# pov-globe2.net
KiCad netlist of a schematic drawn in EAGLE
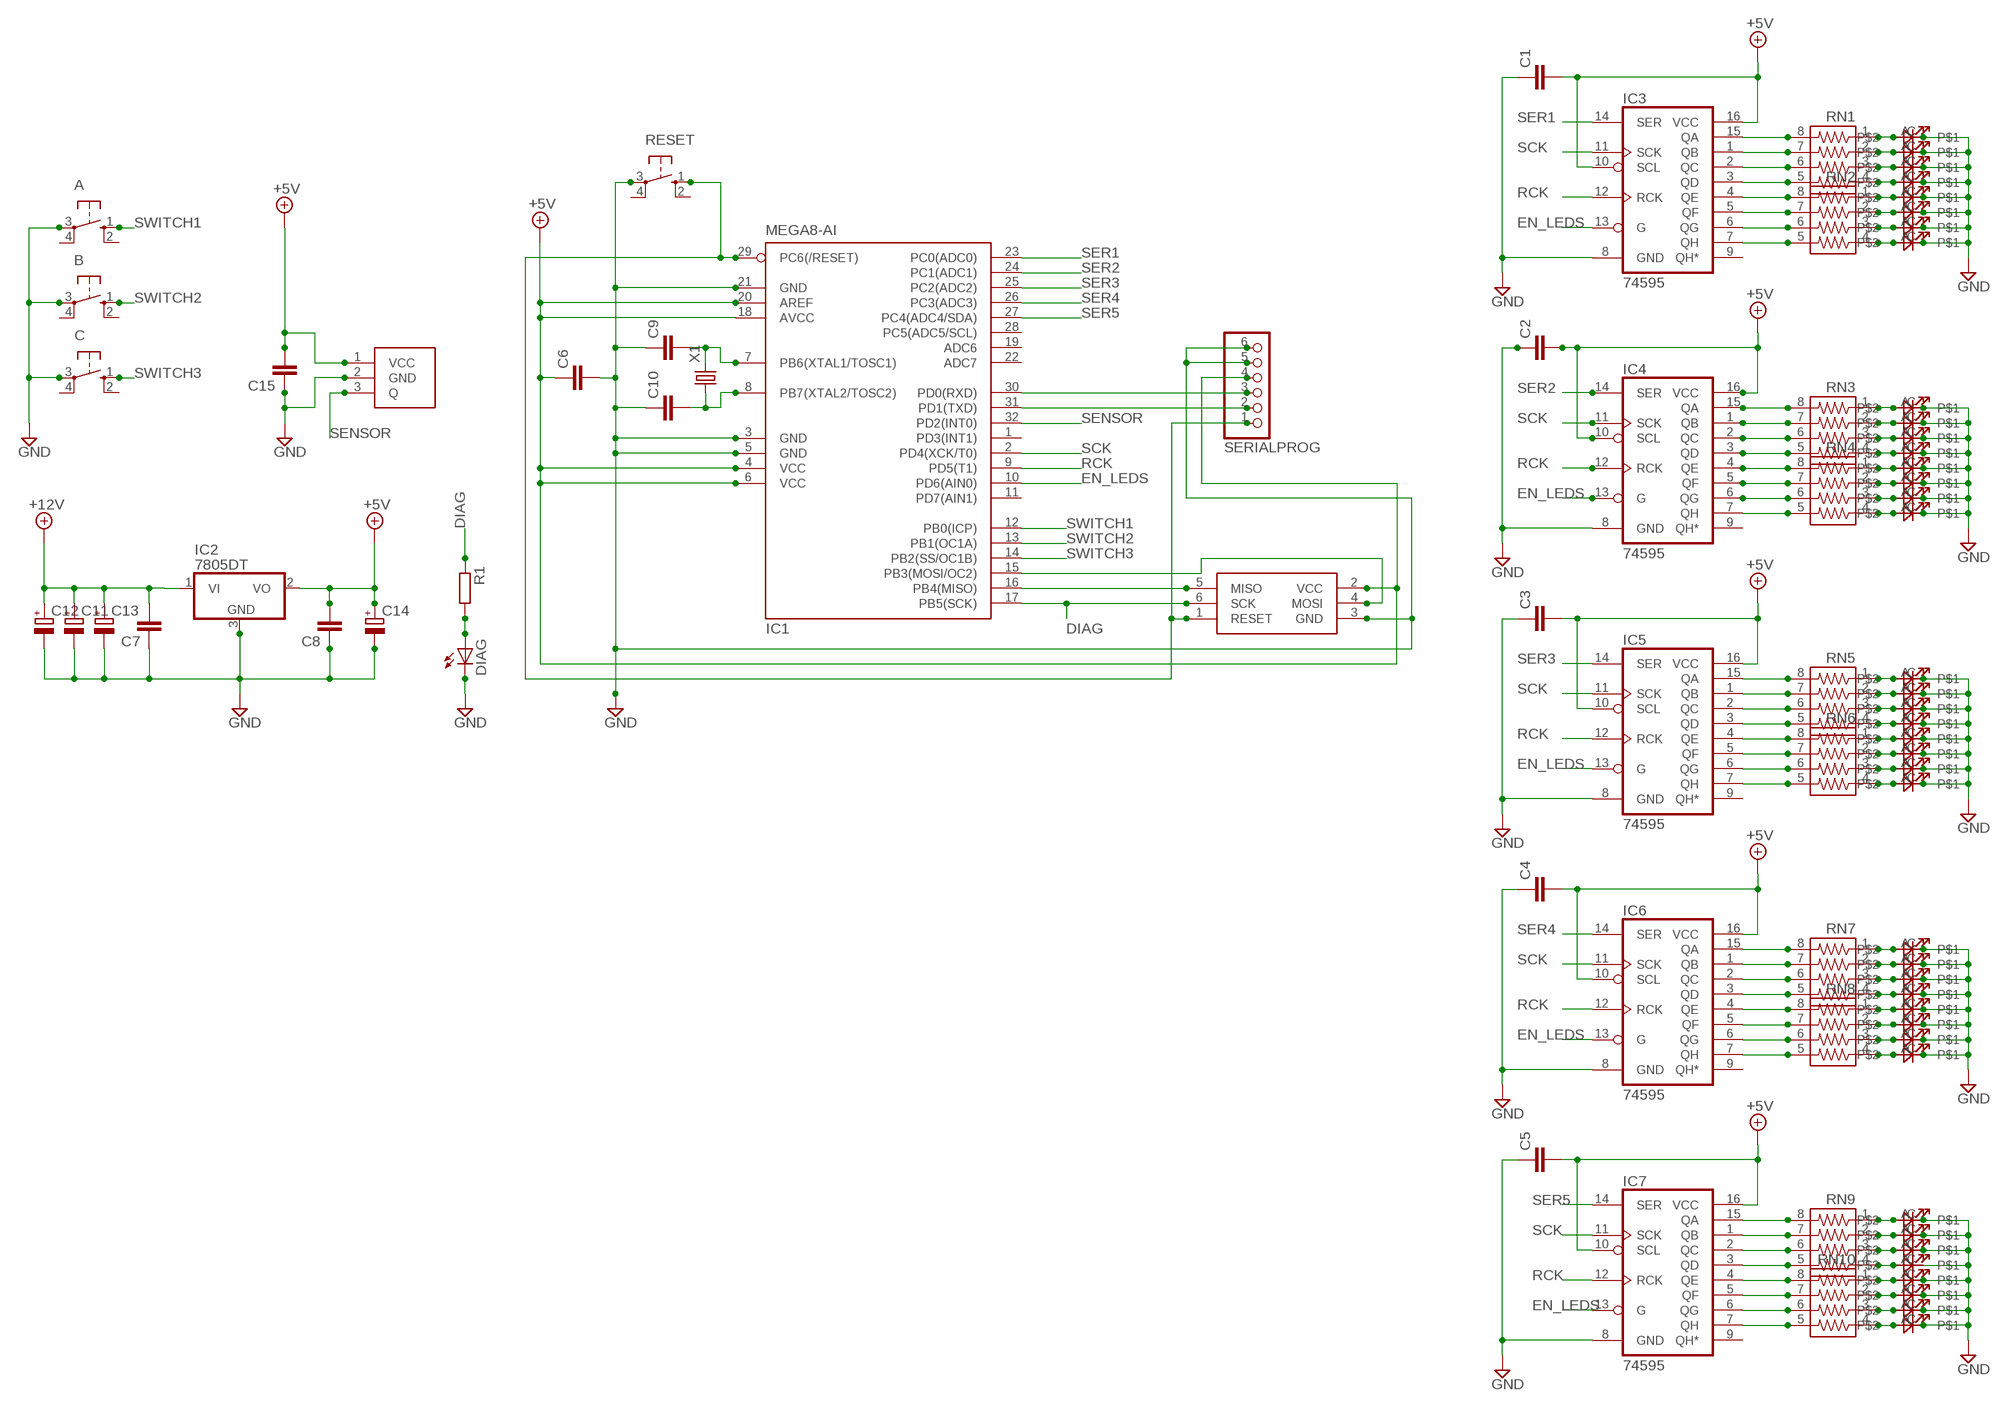
[diagram p0: schematic, sheet 1]

(export (version "E")
  (design (tool "Eeschema 10.0.6"))
  (components
    (comp (ref "0")
      (value "3MMLEDSIDELED1_8MMSIDE")
      (footprint "eagle-import:LED1_8MMSIDE")
      (libsource (lib "eagle-import") (part "3MMLEDSIDELED1_8MMSIDE"))
    )
    (comp (ref "1")
      (value "3MMLEDSIDELED1_8MMSIDE")
      (footprint "eagle-import:LED1_8MMSIDE")
      (libsource (lib "eagle-import") (part "3MMLEDSIDELED1_8MMSIDE"))
    )
    (comp (ref "2")
      (value "3MMLEDSIDELED1_8MMSIDE")
      (footprint "eagle-import:LED1_8MMSIDE")
      (libsource (lib "eagle-import") (part "3MMLEDSIDELED1_8MMSIDE"))
    )
    (comp (ref "3")
      (value "3MMLEDSIDELED1_8MMSIDE")
      (footprint "eagle-import:LED1_8MMSIDE")
      (libsource (lib "eagle-import") (part "3MMLEDSIDELED1_8MMSIDE"))
    )
    (comp (ref "4")
      (value "3MMLEDSIDELED1_8MMSIDE")
      (footprint "eagle-import:LED1_8MMSIDE")
      (libsource (lib "eagle-import") (part "3MMLEDSIDELED1_8MMSIDE"))
    )
    (comp (ref "5")
      (value "3MMLEDSIDELED1_8MMSIDE")
      (footprint "eagle-import:LED1_8MMSIDE")
      (libsource (lib "eagle-import") (part "3MMLEDSIDELED1_8MMSIDE"))
    )
    (comp (ref "6")
      (value "3MMLEDSIDELED1_8MMSIDE")
      (footprint "eagle-import:LED1_8MMSIDE")
      (libsource (lib "eagle-import") (part "3MMLEDSIDELED1_8MMSIDE"))
    )
    (comp (ref "7")
      (value "3MMLEDSIDELED1_8MMSIDE")
      (footprint "eagle-import:LED1_8MMSIDE")
      (libsource (lib "eagle-import") (part "3MMLEDSIDELED1_8MMSIDE"))
    )
    (comp (ref "8")
      (value "3MMLEDSIDELED1_8MMSIDE")
      (footprint "eagle-import:LED1_8MMSIDE")
      (libsource (lib "eagle-import") (part "3MMLEDSIDELED1_8MMSIDE"))
    )
    (comp (ref "9")
      (value "3MMLEDSIDELED1_8MMSIDE")
      (footprint "eagle-import:LED1_8MMSIDE")
      (libsource (lib "eagle-import") (part "3MMLEDSIDELED1_8MMSIDE"))
    )
    (comp (ref "10")
      (value "3MMLEDSIDELED1_8MMSIDE")
      (footprint "eagle-import:LED1_8MMSIDE")
      (libsource (lib "eagle-import") (part "3MMLEDSIDELED1_8MMSIDE"))
    )
    (comp (ref "11")
      (value "3MMLEDSIDELED1_8MMSIDE")
      (footprint "eagle-import:LED1_8MMSIDE")
      (libsource (lib "eagle-import") (part "3MMLEDSIDELED1_8MMSIDE"))
    )
    (comp (ref "12")
      (value "3MMLEDSIDELED1_8MMSIDE")
      (footprint "eagle-import:LED1_8MMSIDE")
      (libsource (lib "eagle-import") (part "3MMLEDSIDELED1_8MMSIDE"))
    )
    (comp (ref "13")
      (value "3MMLEDSIDELED1_8MMSIDE")
      (footprint "eagle-import:LED1_8MMSIDE")
      (libsource (lib "eagle-import") (part "3MMLEDSIDELED1_8MMSIDE"))
    )
    (comp (ref "14")
      (value "3MMLEDSIDELED1_8MMSIDE")
      (footprint "eagle-import:LED1_8MMSIDE")
      (libsource (lib "eagle-import") (part "3MMLEDSIDELED1_8MMSIDE"))
    )
    (comp (ref "15")
      (value "3MMLEDSIDELED1_8MMSIDE")
      (footprint "eagle-import:LED1_8MMSIDE")
      (libsource (lib "eagle-import") (part "3MMLEDSIDELED1_8MMSIDE"))
    )
    (comp (ref "16")
      (value "3MMLEDSIDELED1_8MMSIDE")
      (footprint "eagle-import:LED1_8MMSIDE")
      (libsource (lib "eagle-import") (part "3MMLEDSIDELED1_8MMSIDE"))
    )
    (comp (ref "17")
      (value "3MMLEDSIDELED1_8MMSIDE")
      (footprint "eagle-import:LED1_8MMSIDE")
      (libsource (lib "eagle-import") (part "3MMLEDSIDELED1_8MMSIDE"))
    )
    (comp (ref "18")
      (value "3MMLEDSIDELED1_8MMSIDE")
      (footprint "eagle-import:LED1_8MMSIDE")
      (libsource (lib "eagle-import") (part "3MMLEDSIDELED1_8MMSIDE"))
    )
    (comp (ref "19")
      (value "3MMLEDSIDELED1_8MMSIDE")
      (footprint "eagle-import:LED1_8MMSIDE")
      (libsource (lib "eagle-import") (part "3MMLEDSIDELED1_8MMSIDE"))
    )
    (comp (ref "20")
      (value "3MMLEDSIDELED1_8MMSIDE")
      (footprint "eagle-import:LED1_8MMSIDE")
      (libsource (lib "eagle-import") (part "3MMLEDSIDELED1_8MMSIDE"))
    )
    (comp (ref "21")
      (value "3MMLEDSIDELED1_8MMSIDE")
      (footprint "eagle-import:LED1_8MMSIDE")
      (libsource (lib "eagle-import") (part "3MMLEDSIDELED1_8MMSIDE"))
    )
    (comp (ref "22")
      (value "3MMLEDSIDELED1_8MMSIDE")
      (footprint "eagle-import:LED1_8MMSIDE")
      (libsource (lib "eagle-import") (part "3MMLEDSIDELED1_8MMSIDE"))
    )
    (comp (ref "23")
      (value "3MMLEDSIDELED1_8MMSIDE")
      (footprint "eagle-import:LED1_8MMSIDE")
      (libsource (lib "eagle-import") (part "3MMLEDSIDELED1_8MMSIDE"))
    )
    (comp (ref "24")
      (value "3MMLEDSIDELED1_8MMSIDE")
      (footprint "eagle-import:LED1_8MMSIDE")
      (libsource (lib "eagle-import") (part "3MMLEDSIDELED1_8MMSIDE"))
    )
    (comp (ref "25")
      (value "3MMLEDSIDELED1_8MMSIDE")
      (footprint "eagle-import:LED1_8MMSIDE")
      (libsource (lib "eagle-import") (part "3MMLEDSIDELED1_8MMSIDE"))
    )
    (comp (ref "26")
      (value "3MMLEDSIDELED1_8MMSIDE")
      (footprint "eagle-import:LED1_8MMSIDE")
      (libsource (lib "eagle-import") (part "3MMLEDSIDELED1_8MMSIDE"))
    )
    (comp (ref "27")
      (value "3MMLEDSIDELED1_8MMSIDE")
      (footprint "eagle-import:LED1_8MMSIDE")
      (libsource (lib "eagle-import") (part "3MMLEDSIDELED1_8MMSIDE"))
    )
    (comp (ref "28")
      (value "3MMLEDSIDELED1_8MMSIDE")
      (footprint "eagle-import:LED1_8MMSIDE")
      (libsource (lib "eagle-import") (part "3MMLEDSIDELED1_8MMSIDE"))
    )
    (comp (ref "29")
      (value "3MMLEDSIDELED1_8MMSIDE")
      (footprint "eagle-import:LED1_8MMSIDE")
      (libsource (lib "eagle-import") (part "3MMLEDSIDELED1_8MMSIDE"))
    )
    (comp (ref "30")
      (value "3MMLEDSIDELED1_8MMSIDE")
      (footprint "eagle-import:LED1_8MMSIDE")
      (libsource (lib "eagle-import") (part "3MMLEDSIDELED1_8MMSIDE"))
    )
    (comp (ref "31")
      (value "3MMLEDSIDELED1_8MMSIDE")
      (footprint "eagle-import:LED1_8MMSIDE")
      (libsource (lib "eagle-import") (part "3MMLEDSIDELED1_8MMSIDE"))
    )
    (comp (ref "32")
      (value "3MMLEDSIDELED1_8MMSIDE")
      (footprint "eagle-import:LED1_8MMSIDE")
      (libsource (lib "eagle-import") (part "3MMLEDSIDELED1_8MMSIDE"))
    )
    (comp (ref "33")
      (value "3MMLEDSIDELED1_8MMSIDE")
      (footprint "eagle-import:LED1_8MMSIDE")
      (libsource (lib "eagle-import") (part "3MMLEDSIDELED1_8MMSIDE"))
    )
    (comp (ref "34")
      (value "3MMLEDSIDELED1_8MMSIDE")
      (footprint "eagle-import:LED1_8MMSIDE")
      (libsource (lib "eagle-import") (part "3MMLEDSIDELED1_8MMSIDE"))
    )
    (comp (ref "35")
      (value "3MMLEDSIDELED1_8MMSIDE")
      (footprint "eagle-import:LED1_8MMSIDE")
      (libsource (lib "eagle-import") (part "3MMLEDSIDELED1_8MMSIDE"))
    )
    (comp (ref "36")
      (value "3MMLEDSIDELED1_8MMSIDE")
      (footprint "eagle-import:LED1_8MMSIDE")
      (libsource (lib "eagle-import") (part "3MMLEDSIDELED1_8MMSIDE"))
    )
    (comp (ref "37")
      (value "3MMLEDSIDELED1_8MMSIDE")
      (footprint "eagle-import:LED1_8MMSIDE")
      (libsource (lib "eagle-import") (part "3MMLEDSIDELED1_8MMSIDE"))
    )
    (comp (ref "38")
      (value "3MMLEDSIDELED1_8MMSIDE")
      (footprint "eagle-import:LED1_8MMSIDE")
      (libsource (lib "eagle-import") (part "3MMLEDSIDELED1_8MMSIDE"))
    )
    (comp (ref "39")
      (value "3MMLEDSIDELED1_8MMSIDE")
      (footprint "eagle-import:LED1_8MMSIDE")
      (libsource (lib "eagle-import") (part "3MMLEDSIDELED1_8MMSIDE"))
    )
    (comp (ref "A")
      (value "10-XX")
      (footprint "eagle-import:B3F-10XX")
      (libsource (lib "eagle-import") (part "10-XX"))
    )
    (comp (ref "B")
      (value "10-XX")
      (footprint "eagle-import:B3F-10XX")
      (libsource (lib "eagle-import") (part "10-XX"))
    )
    (comp (ref "C")
      (value "10-XX")
      (footprint "eagle-import:B3F-10XX")
      (libsource (lib "eagle-import") (part "10-XX"))
    )
    (comp (ref "C1")
      (value "C-EUC0805")
      (footprint "eagle-import:C0805")
      (libsource (lib "eagle-import") (part "C-EUC0805"))
    )
    (comp (ref "C2")
      (value "C-EUC0805")
      (footprint "eagle-import:C0805")
      (libsource (lib "eagle-import") (part "C-EUC0805"))
    )
    (comp (ref "C3")
      (value "C-EUC0805")
      (footprint "eagle-import:C0805")
      (libsource (lib "eagle-import") (part "C-EUC0805"))
    )
    (comp (ref "C4")
      (value "C-EUC0805")
      (footprint "eagle-import:C0805")
      (libsource (lib "eagle-import") (part "C-EUC0805"))
    )
    (comp (ref "C5")
      (value "C-EUC0805")
      (footprint "eagle-import:C0805")
      (libsource (lib "eagle-import") (part "C-EUC0805"))
    )
    (comp (ref "C6")
      (value "C-EUC0805")
      (footprint "eagle-import:C0805")
      (libsource (lib "eagle-import") (part "C-EUC0805"))
    )
    (comp (ref "C7")
      (value "C-EUC0805")
      (footprint "eagle-import:C0805")
      (libsource (lib "eagle-import") (part "C-EUC0805"))
    )
    (comp (ref "C8")
      (value "C-EUC0805")
      (footprint "eagle-import:C0805")
      (libsource (lib "eagle-import") (part "C-EUC0805"))
    )
    (comp (ref "C9")
      (value "C-EUC0805")
      (footprint "eagle-import:C0805")
      (libsource (lib "eagle-import") (part "C-EUC0805"))
    )
    (comp (ref "C10")
      (value "C-EUC0805")
      (footprint "eagle-import:C0805")
      (libsource (lib "eagle-import") (part "C-EUC0805"))
    )
    (comp (ref "C11")
      (value "CPOL-EUE2-5")
      (footprint "eagle-import:E2-5")
      (libsource (lib "eagle-import") (part "CPOL-EUE2-5"))
    )
    (comp (ref "C12")
      (value "CPOL-EUE2-5")
      (footprint "eagle-import:E2-5")
      (libsource (lib "eagle-import") (part "CPOL-EUE2-5"))
    )
    (comp (ref "C13")
      (value "CPOL-EUE2-5")
      (footprint "eagle-import:E2-5")
      (libsource (lib "eagle-import") (part "CPOL-EUE2-5"))
    )
    (comp (ref "C14")
      (value "CPOL-EUE2-5")
      (footprint "eagle-import:E2-5")
      (libsource (lib "eagle-import") (part "CPOL-EUE2-5"))
    )
    (comp (ref "C15")
      (value "C-EUC0805")
      (footprint "eagle-import:C0805")
      (libsource (lib "eagle-import") (part "C-EUC0805"))
    )
    (comp (ref "DIAG")
      (value "LEDCHIP-LED0805")
      (footprint "eagle-import:CHIP-LED0805")
      (libsource (lib "eagle-import") (part "LEDCHIP-LED0805"))
    )
    (comp (ref "IC1")
      (value "MEGA8-AI")
      (footprint "eagle-import:TQFP32-08")
      (libsource (lib "eagle-import") (part "MEGA8-AI"))
    )
    (comp (ref "IC2")
      (value "7805DT")
      (footprint "eagle-import:TO252")
      (libsource (lib "eagle-import") (part "78DT05"))
    )
    (comp (ref "IC3")
      (value "74595")
      (footprint "eagle-import:TSSOP16")
      (libsource (lib "eagle-import") (part "74595"))
    )
    (comp (ref "IC4")
      (value "74595")
      (footprint "eagle-import:TSSOP16")
      (libsource (lib "eagle-import") (part "74595"))
    )
    (comp (ref "IC5")
      (value "74595")
      (footprint "eagle-import:TSSOP16")
      (libsource (lib "eagle-import") (part "74595"))
    )
    (comp (ref "IC6")
      (value "74595")
      (footprint "eagle-import:TSSOP16")
      (libsource (lib "eagle-import") (part "74595"))
    )
    (comp (ref "IC7")
      (value "74595")
      (footprint "eagle-import:TSSOP16")
      (libsource (lib "eagle-import") (part "74595"))
    )
    (comp (ref "ICSP")
      (value "TAG_CONN_AVR")
      (footprint "eagle-import:TC2030-MCP-NL")
      (libsource (lib "eagle-import") (part "TAG_CONN_AVR"))
    )
    (comp (ref "R1")
      (value "R-EU_R0805")
      (footprint "eagle-import:R0805")
      (libsource (lib "eagle-import") (part "R-EU_R0805"))
    )
    (comp (ref "RESET")
      (value "10-XX")
      (footprint "eagle-import:B3F-10XX")
      (libsource (lib "eagle-import") (part "10-XX"))
    )
    (comp (ref "RN1")
      (value "741-8")
      (footprint "eagle-import:741-8")
      (libsource (lib "eagle-import") (part "741-8"))
    )
    (comp (ref "RN2")
      (value "741-8")
      (footprint "eagle-import:741-8")
      (libsource (lib "eagle-import") (part "741-8"))
    )
    (comp (ref "RN3")
      (value "741-8")
      (footprint "eagle-import:741-8")
      (libsource (lib "eagle-import") (part "741-8"))
    )
    (comp (ref "RN4")
      (value "741-8")
      (footprint "eagle-import:741-8")
      (libsource (lib "eagle-import") (part "741-8"))
    )
    (comp (ref "RN5")
      (value "741-8")
      (footprint "eagle-import:741-8")
      (libsource (lib "eagle-import") (part "741-8"))
    )
    (comp (ref "RN6")
      (value "741-8")
      (footprint "eagle-import:741-8")
      (libsource (lib "eagle-import") (part "741-8"))
    )
    (comp (ref "RN7")
      (value "741-8")
      (footprint "eagle-import:741-8")
      (libsource (lib "eagle-import") (part "741-8"))
    )
    (comp (ref "RN8")
      (value "741-8")
      (footprint "eagle-import:741-8")
      (libsource (lib "eagle-import") (part "741-8"))
    )
    (comp (ref "RN9")
      (value "741-8")
      (footprint "eagle-import:741-8")
      (libsource (lib "eagle-import") (part "741-8"))
    )
    (comp (ref "RN10")
      (value "741-8")
      (footprint "eagle-import:741-8")
      (libsource (lib "eagle-import") (part "741-8"))
    )
    (comp (ref "S1")
      (value "3144HALLSWITCH")
      (footprint "eagle-import:3144HALLSWITCH")
      (libsource (lib "eagle-import") (part "3144HALLSWITCH"))
    )
    (comp (ref "SERIALPROG")
      (value "PINHD-1X6")
      (footprint "eagle-import:1X06")
      (libsource (lib "eagle-import") (part "PINHD-1X6"))
    )
    (comp (ref "X1")
      (value "CRYSTALHC49U-V")
      (footprint "eagle-import:HC49U-V")
      (libsource (lib "eagle-import") (part "CRYSTALHC49U-V"))
    )
  )
  (nets
    (net (code "1") (name "+5V") (class "Default")
      (node (ref "C1") (pin "2") (pinfunction "2_2") (pintype "passive"))
      (node (ref "C14") (pin "+") (pinfunction "+_+") (pintype "passive"))
      (node (ref "C15") (pin "2") (pinfunction "2_2") (pintype "passive"))
      (node (ref "C2") (pin "2") (pinfunction "2_2") (pintype "passive"))
      (node (ref "C3") (pin "2") (pinfunction "2_2") (pintype "passive"))
      (node (ref "C4") (pin "2") (pinfunction "2_2") (pintype "passive"))
      (node (ref "C5") (pin "2") (pinfunction "2_2") (pintype "passive"))
      (node (ref "C6") (pin "1") (pinfunction "1_1") (pintype "passive"))
      (node (ref "C8") (pin "2") (pinfunction "2_2") (pintype "passive"))
      (node (ref "IC1") (pin "18") (pinfunction "AVCC_18") (pintype "power_in"))
      (node (ref "IC1") (pin "20") (pinfunction "AREF_20") (pintype "passive"))
      (node (ref "IC1") (pin "4") (pinfunction "VCC_4") (pintype "power_in"))
      (node (ref "IC1") (pin "6") (pinfunction "VCC_6") (pintype "power_in"))
      (node (ref "IC2") (pin "2") (pinfunction "VO_2") (pintype "passive"))
      (node (ref "IC3") (pin "10") (pinfunction "SCL_10") (pintype "input"))
      (node (ref "IC3") (pin "16") (pinfunction "VCC_16") (pintype "power_in"))
      (node (ref "IC4") (pin "10") (pinfunction "SCL_10") (pintype "input"))
      (node (ref "IC4") (pin "16") (pinfunction "VCC_16") (pintype "power_in"))
      (node (ref "IC5") (pin "10") (pinfunction "SCL_10") (pintype "input"))
      (node (ref "IC5") (pin "16") (pinfunction "VCC_16") (pintype "power_in"))
      (node (ref "IC6") (pin "10") (pinfunction "SCL_10") (pintype "input"))
      (node (ref "IC6") (pin "16") (pinfunction "VCC_16") (pintype "power_in"))
      (node (ref "IC7") (pin "10") (pinfunction "SCL_10") (pintype "input"))
      (node (ref "IC7") (pin "16") (pinfunction "VCC_16") (pintype "power_in"))
      (node (ref "ICSP") (pin "2") (pinfunction "VCC_2") (pintype "power_in"))
      (node (ref "S1") (pin "1") (pinfunction "VCC_1") (pintype "power_in"))
      (node (ref "SERIALPROG") (pin "4") (pinfunction "4_4") (pintype "passive"))
    )
    (net (code "2") (name "+12V") (class "Default")
      (node (ref "C11") (pin "+") (pinfunction "+_+") (pintype "passive"))
      (node (ref "C12") (pin "+") (pinfunction "+_+") (pintype "passive"))
      (node (ref "C13") (pin "+") (pinfunction "+_+") (pintype "passive"))
      (node (ref "C7") (pin "2") (pinfunction "2_2") (pintype "passive"))
      (node (ref "IC2") (pin "1") (pinfunction "VI_1") (pintype "input"))
    )
    (net (code "3") (name "/DIAG") (class "Default")
      (node (ref "IC1") (pin "17") (pinfunction "PB5(SCK)_17") (pintype "bidirectional"))
      (node (ref "ICSP") (pin "6") (pinfunction "SCK_6") (pintype "bidirectional"))
      (node (ref "R1") (pin "1") (pinfunction "1_1") (pintype "passive"))
    )
    (net (code "4") (name "/EN_LEDS") (class "Default")
      (node (ref "IC1") (pin "10") (pinfunction "PD6(AIN0)_10") (pintype "bidirectional"))
      (node (ref "IC3") (pin "13") (pinfunction "G_13") (pintype "input"))
      (node (ref "IC4") (pin "13") (pinfunction "G_13") (pintype "input"))
      (node (ref "IC5") (pin "13") (pinfunction "G_13") (pintype "input"))
      (node (ref "IC6") (pin "13") (pinfunction "G_13") (pintype "input"))
      (node (ref "IC7") (pin "13") (pinfunction "G_13") (pintype "input"))
    )
    (net (code "5") (name "/RCK") (class "Default")
      (node (ref "IC1") (pin "9") (pinfunction "PD5(T1)_9") (pintype "bidirectional"))
      (node (ref "IC3") (pin "12") (pinfunction "RCK_12") (pintype "input"))
      (node (ref "IC4") (pin "12") (pinfunction "RCK_12") (pintype "input"))
      (node (ref "IC5") (pin "12") (pinfunction "RCK_12") (pintype "input"))
      (node (ref "IC6") (pin "12") (pinfunction "RCK_12") (pintype "input"))
      (node (ref "IC7") (pin "12") (pinfunction "RCK_12") (pintype "input"))
    )
    (net (code "6") (name "/SCK") (class "Default")
      (node (ref "IC1") (pin "2") (pinfunction "PD4(XCK/T0)_2") (pintype "bidirectional"))
      (node (ref "IC3") (pin "11") (pinfunction "SCK_11") (pintype "input"))
      (node (ref "IC4") (pin "11") (pinfunction "SCK_11") (pintype "input"))
      (node (ref "IC5") (pin "11") (pinfunction "SCK_11") (pintype "input"))
      (node (ref "IC6") (pin "11") (pinfunction "SCK_11") (pintype "input"))
      (node (ref "IC7") (pin "11") (pinfunction "SCK_11") (pintype "input"))
    )
    (net (code "7") (name "/SENSOR") (class "Default")
      (node (ref "IC1") (pin "32") (pinfunction "PD2(INT0)_32") (pintype "bidirectional"))
      (node (ref "S1") (pin "3") (pinfunction "Q_3") (pintype "open_collector"))
    )
    (net (code "8") (name "/SER1") (class "Default")
      (node (ref "IC1") (pin "23") (pinfunction "PC0(ADC0)_23") (pintype "bidirectional"))
      (node (ref "IC3") (pin "14") (pinfunction "SER_14") (pintype "input"))
    )
    (net (code "9") (name "/SER2") (class "Default")
      (node (ref "IC1") (pin "24") (pinfunction "PC1(ADC1)_24") (pintype "bidirectional"))
      (node (ref "IC4") (pin "14") (pinfunction "SER_14") (pintype "input"))
    )
    (net (code "10") (name "/SER3") (class "Default")
      (node (ref "IC1") (pin "25") (pinfunction "PC2(ADC2)_25") (pintype "bidirectional"))
      (node (ref "IC5") (pin "14") (pinfunction "SER_14") (pintype "input"))
    )
    (net (code "11") (name "/SER4") (class "Default")
      (node (ref "IC1") (pin "26") (pinfunction "PC3(ADC3)_26") (pintype "bidirectional"))
      (node (ref "IC6") (pin "14") (pinfunction "SER_14") (pintype "input"))
    )
    (net (code "12") (name "/SER5") (class "Default")
      (node (ref "IC1") (pin "27") (pinfunction "PC4(ADC4/SDA)_27") (pintype "bidirectional"))
      (node (ref "IC7") (pin "14") (pinfunction "SER_14") (pintype "input"))
    )
    (net (code "13") (name "/SWITCH1") (class "Default")
      (node (ref "A") (pin "1") (pinfunction "S_1") (pintype "passive"))
      (node (ref "IC1") (pin "12") (pinfunction "PB0(ICP)_12") (pintype "bidirectional"))
    )
    (net (code "14") (name "/SWITCH2") (class "Default")
      (node (ref "B") (pin "1") (pinfunction "S_1") (pintype "passive"))
      (node (ref "IC1") (pin "13") (pinfunction "PB1(OC1A)_13") (pintype "bidirectional"))
    )
    (net (code "15") (name "/SWITCH3") (class "Default")
      (node (ref "C") (pin "1") (pinfunction "S_1") (pintype "passive"))
      (node (ref "IC1") (pin "14") (pinfunction "PB2(SS/OC1B)_14") (pintype "bidirectional"))
    )
    (net (code "16") (name "GND") (class "Default")
      (node (ref "0") (pin "C") (pinfunction "P$2_C") (pintype "bidirectional"))
      (node (ref "1") (pin "C") (pinfunction "P$2_C") (pintype "bidirectional"))
      (node (ref "10") (pin "C") (pinfunction "P$2_C") (pintype "bidirectional"))
      (node (ref "11") (pin "C") (pinfunction "P$2_C") (pintype "bidirectional"))
      (node (ref "12") (pin "C") (pinfunction "P$2_C") (pintype "bidirectional"))
      (node (ref "13") (pin "C") (pinfunction "P$2_C") (pintype "bidirectional"))
      (node (ref "14") (pin "C") (pinfunction "P$2_C") (pintype "bidirectional"))
      (node (ref "15") (pin "C") (pinfunction "P$2_C") (pintype "bidirectional"))
      (node (ref "16") (pin "C") (pinfunction "P$2_C") (pintype "bidirectional"))
      (node (ref "17") (pin "C") (pinfunction "P$2_C") (pintype "bidirectional"))
      (node (ref "18") (pin "C") (pinfunction "P$2_C") (pintype "bidirectional"))
      (node (ref "19") (pin "C") (pinfunction "P$2_C") (pintype "bidirectional"))
      (node (ref "2") (pin "C") (pinfunction "P$2_C") (pintype "bidirectional"))
      (node (ref "20") (pin "C") (pinfunction "P$2_C") (pintype "bidirectional"))
      (node (ref "21") (pin "C") (pinfunction "P$2_C") (pintype "bidirectional"))
      (node (ref "22") (pin "C") (pinfunction "P$2_C") (pintype "bidirectional"))
      (node (ref "23") (pin "C") (pinfunction "P$2_C") (pintype "bidirectional"))
      (node (ref "24") (pin "C") (pinfunction "P$2_C") (pintype "bidirectional"))
      (node (ref "25") (pin "C") (pinfunction "P$2_C") (pintype "bidirectional"))
      (node (ref "26") (pin "C") (pinfunction "P$2_C") (pintype "bidirectional"))
      (node (ref "27") (pin "C") (pinfunction "P$2_C") (pintype "bidirectional"))
      (node (ref "28") (pin "C") (pinfunction "P$2_C") (pintype "bidirectional"))
      (node (ref "29") (pin "C") (pinfunction "P$2_C") (pintype "bidirectional"))
      (node (ref "3") (pin "C") (pinfunction "P$2_C") (pintype "bidirectional"))
      (node (ref "30") (pin "C") (pinfunction "P$2_C") (pintype "bidirectional"))
      (node (ref "31") (pin "C") (pinfunction "P$2_C") (pintype "bidirectional"))
      (node (ref "32") (pin "C") (pinfunction "P$2_C") (pintype "bidirectional"))
      (node (ref "33") (pin "C") (pinfunction "P$2_C") (pintype "bidirectional"))
      (node (ref "34") (pin "C") (pinfunction "P$2_C") (pintype "bidirectional"))
      (node (ref "35") (pin "C") (pinfunction "P$2_C") (pintype "bidirectional"))
      (node (ref "36") (pin "C") (pinfunction "P$2_C") (pintype "bidirectional"))
      (node (ref "37") (pin "C") (pinfunction "P$2_C") (pintype "bidirectional"))
      (node (ref "38") (pin "C") (pinfunction "P$2_C") (pintype "bidirectional"))
      (node (ref "39") (pin "C") (pinfunction "P$2_C") (pintype "bidirectional"))
      (node (ref "4") (pin "C") (pinfunction "P$2_C") (pintype "bidirectional"))
      (node (ref "5") (pin "C") (pinfunction "P$2_C") (pintype "bidirectional"))
      (node (ref "6") (pin "C") (pinfunction "P$2_C") (pintype "bidirectional"))
      (node (ref "7") (pin "C") (pinfunction "P$2_C") (pintype "bidirectional"))
      (node (ref "8") (pin "C") (pinfunction "P$2_C") (pintype "bidirectional"))
      (node (ref "9") (pin "C") (pinfunction "P$2_C") (pintype "bidirectional"))
      (node (ref "A") (pin "3") (pinfunction "P_3") (pintype "passive"))
      (node (ref "B") (pin "3") (pinfunction "P_3") (pintype "passive"))
      (node (ref "C") (pin "3") (pinfunction "P_3") (pintype "passive"))
      (node (ref "C1") (pin "1") (pinfunction "1_1") (pintype "passive"))
      (node (ref "C10") (pin "1") (pinfunction "1_1") (pintype "passive"))
      (node (ref "C11") (pin "-") (pinfunction "-_-") (pintype "passive"))
      (node (ref "C12") (pin "-") (pinfunction "-_-") (pintype "passive"))
      (node (ref "C13") (pin "-") (pinfunction "-_-") (pintype "passive"))
      (node (ref "C14") (pin "-") (pinfunction "-_-") (pintype "passive"))
      (node (ref "C15") (pin "1") (pinfunction "1_1") (pintype "passive"))
      (node (ref "C2") (pin "1") (pinfunction "1_1") (pintype "passive"))
      (node (ref "C3") (pin "1") (pinfunction "1_1") (pintype "passive"))
      (node (ref "C4") (pin "1") (pinfunction "1_1") (pintype "passive"))
      (node (ref "C5") (pin "1") (pinfunction "1_1") (pintype "passive"))
      (node (ref "C6") (pin "2") (pinfunction "2_2") (pintype "passive"))
      (node (ref "C7") (pin "1") (pinfunction "1_1") (pintype "passive"))
      (node (ref "C8") (pin "1") (pinfunction "1_1") (pintype "passive"))
      (node (ref "C9") (pin "1") (pinfunction "1_1") (pintype "passive"))
      (node (ref "DIAG") (pin "C") (pinfunction "C_C") (pintype "passive"))
      (node (ref "IC1") (pin "21") (pinfunction "GND_21") (pintype "power_in"))
      (node (ref "IC1") (pin "3") (pinfunction "GND_3") (pintype "power_in"))
      (node (ref "IC1") (pin "5") (pinfunction "GND_5") (pintype "power_in"))
      (node (ref "IC2") (pin "3") (pinfunction "GND_3") (pintype "passive"))
      (node (ref "IC3") (pin "8") (pinfunction "GND_8") (pintype "power_in"))
      (node (ref "IC4") (pin "8") (pinfunction "GND_8") (pintype "power_in"))
      (node (ref "IC5") (pin "8") (pinfunction "GND_8") (pintype "power_in"))
      (node (ref "IC6") (pin "8") (pinfunction "GND_8") (pintype "power_in"))
      (node (ref "IC7") (pin "8") (pinfunction "GND_8") (pintype "power_in"))
      (node (ref "ICSP") (pin "3") (pinfunction "GND_3") (pintype "power_in"))
      (node (ref "RESET") (pin "3") (pinfunction "P_3") (pintype "passive"))
      (node (ref "S1") (pin "2") (pinfunction "GND_2") (pintype "power_in"))
      (node (ref "SERIALPROG") (pin "5") (pinfunction "5_5") (pintype "passive"))
      (node (ref "SERIALPROG") (pin "6") (pinfunction "6_6") (pintype "passive"))
    )
    (net (code "17") (name "Net-(0-P$1)") (class "Default")
      (node (ref "0") (pin "A") (pinfunction "P$1_A") (pintype "bidirectional"))
      (node (ref "RN1") (pin "1") (pinfunction "1_1") (pintype "passive"))
    )
    (net (code "18") (name "Net-(1-P$1)") (class "Default")
      (node (ref "1") (pin "A") (pinfunction "P$1_A") (pintype "bidirectional"))
      (node (ref "RN1") (pin "2") (pinfunction "2_2") (pintype "passive"))
    )
    (net (code "19") (name "Net-(2-P$1)") (class "Default")
      (node (ref "2") (pin "A") (pinfunction "P$1_A") (pintype "bidirectional"))
      (node (ref "RN1") (pin "3") (pinfunction "3_3") (pintype "passive"))
    )
    (net (code "20") (name "Net-(3-P$1)") (class "Default")
      (node (ref "3") (pin "A") (pinfunction "P$1_A") (pintype "bidirectional"))
      (node (ref "RN1") (pin "4") (pinfunction "4_4") (pintype "passive"))
    )
    (net (code "21") (name "Net-(4-P$1)") (class "Default")
      (node (ref "4") (pin "A") (pinfunction "P$1_A") (pintype "bidirectional"))
      (node (ref "RN2") (pin "1") (pinfunction "1_1") (pintype "passive"))
    )
    (net (code "22") (name "Net-(5-P$1)") (class "Default")
      (node (ref "5") (pin "A") (pinfunction "P$1_A") (pintype "bidirectional"))
      (node (ref "RN2") (pin "2") (pinfunction "2_2") (pintype "passive"))
    )
    (net (code "23") (name "Net-(6-P$1)") (class "Default")
      (node (ref "6") (pin "A") (pinfunction "P$1_A") (pintype "bidirectional"))
      (node (ref "RN2") (pin "3") (pinfunction "3_3") (pintype "passive"))
    )
    (net (code "24") (name "Net-(7-P$1)") (class "Default")
      (node (ref "7") (pin "A") (pinfunction "P$1_A") (pintype "bidirectional"))
      (node (ref "RN2") (pin "4") (pinfunction "4_4") (pintype "passive"))
    )
    (net (code "25") (name "Net-(8-P$1)") (class "Default")
      (node (ref "8") (pin "A") (pinfunction "P$1_A") (pintype "bidirectional"))
      (node (ref "RN3") (pin "1") (pinfunction "1_1") (pintype "passive"))
    )
    (net (code "26") (name "Net-(9-P$1)") (class "Default")
      (node (ref "9") (pin "A") (pinfunction "P$1_A") (pintype "bidirectional"))
      (node (ref "RN3") (pin "2") (pinfunction "2_2") (pintype "passive"))
    )
    (net (code "27") (name "Net-(10-P$1)") (class "Default")
      (node (ref "10") (pin "A") (pinfunction "P$1_A") (pintype "bidirectional"))
      (node (ref "RN3") (pin "3") (pinfunction "3_3") (pintype "passive"))
    )
    (net (code "28") (name "Net-(11-P$1)") (class "Default")
      (node (ref "11") (pin "A") (pinfunction "P$1_A") (pintype "bidirectional"))
      (node (ref "RN3") (pin "4") (pinfunction "4_4") (pintype "passive"))
    )
    (net (code "29") (name "Net-(12-P$1)") (class "Default")
      (node (ref "12") (pin "A") (pinfunction "P$1_A") (pintype "bidirectional"))
      (node (ref "RN4") (pin "1") (pinfunction "1_1") (pintype "passive"))
    )
    (net (code "30") (name "Net-(13-P$1)") (class "Default")
      (node (ref "13") (pin "A") (pinfunction "P$1_A") (pintype "bidirectional"))
      (node (ref "RN4") (pin "2") (pinfunction "2_2") (pintype "passive"))
    )
    (net (code "31") (name "Net-(14-P$1)") (class "Default")
      (node (ref "14") (pin "A") (pinfunction "P$1_A") (pintype "bidirectional"))
      (node (ref "RN4") (pin "3") (pinfunction "3_3") (pintype "passive"))
    )
    (net (code "32") (name "Net-(15-P$1)") (class "Default")
      (node (ref "15") (pin "A") (pinfunction "P$1_A") (pintype "bidirectional"))
      (node (ref "RN4") (pin "4") (pinfunction "4_4") (pintype "passive"))
    )
    (net (code "33") (name "Net-(16-P$1)") (class "Default")
      (node (ref "16") (pin "A") (pinfunction "P$1_A") (pintype "bidirectional"))
      (node (ref "RN5") (pin "1") (pinfunction "1_1") (pintype "passive"))
    )
    (net (code "34") (name "Net-(17-P$1)") (class "Default")
      (node (ref "17") (pin "A") (pinfunction "P$1_A") (pintype "bidirectional"))
      (node (ref "RN5") (pin "2") (pinfunction "2_2") (pintype "passive"))
    )
    (net (code "35") (name "Net-(18-P$1)") (class "Default")
      (node (ref "18") (pin "A") (pinfunction "P$1_A") (pintype "bidirectional"))
      (node (ref "RN5") (pin "3") (pinfunction "3_3") (pintype "passive"))
    )
    (net (code "36") (name "Net-(19-P$1)") (class "Default")
      (node (ref "19") (pin "A") (pinfunction "P$1_A") (pintype "bidirectional"))
      (node (ref "RN5") (pin "4") (pinfunction "4_4") (pintype "passive"))
    )
    (net (code "37") (name "Net-(20-P$1)") (class "Default")
      (node (ref "20") (pin "A") (pinfunction "P$1_A") (pintype "bidirectional"))
      (node (ref "RN6") (pin "1") (pinfunction "1_1") (pintype "passive"))
    )
    (net (code "38") (name "Net-(21-P$1)") (class "Default")
      (node (ref "21") (pin "A") (pinfunction "P$1_A") (pintype "bidirectional"))
      (node (ref "RN6") (pin "2") (pinfunction "2_2") (pintype "passive"))
    )
    (net (code "39") (name "Net-(22-P$1)") (class "Default")
      (node (ref "22") (pin "A") (pinfunction "P$1_A") (pintype "bidirectional"))
      (node (ref "RN6") (pin "3") (pinfunction "3_3") (pintype "passive"))
    )
    (net (code "40") (name "Net-(23-P$1)") (class "Default")
      (node (ref "23") (pin "A") (pinfunction "P$1_A") (pintype "bidirectional"))
      (node (ref "RN6") (pin "4") (pinfunction "4_4") (pintype "passive"))
    )
    (net (code "41") (name "Net-(24-P$1)") (class "Default")
      (node (ref "24") (pin "A") (pinfunction "P$1_A") (pintype "bidirectional"))
      (node (ref "RN7") (pin "1") (pinfunction "1_1") (pintype "passive"))
    )
    (net (code "42") (name "Net-(25-P$1)") (class "Default")
      (node (ref "25") (pin "A") (pinfunction "P$1_A") (pintype "bidirectional"))
      (node (ref "RN7") (pin "2") (pinfunction "2_2") (pintype "passive"))
    )
    (net (code "43") (name "Net-(26-P$1)") (class "Default")
      (node (ref "26") (pin "A") (pinfunction "P$1_A") (pintype "bidirectional"))
      (node (ref "RN7") (pin "3") (pinfunction "3_3") (pintype "passive"))
    )
    (net (code "44") (name "Net-(27-P$1)") (class "Default")
      (node (ref "27") (pin "A") (pinfunction "P$1_A") (pintype "bidirectional"))
      (node (ref "RN7") (pin "4") (pinfunction "4_4") (pintype "passive"))
    )
    (net (code "45") (name "Net-(28-P$1)") (class "Default")
      (node (ref "28") (pin "A") (pinfunction "P$1_A") (pintype "bidirectional"))
      (node (ref "RN8") (pin "1") (pinfunction "1_1") (pintype "passive"))
    )
    (net (code "46") (name "Net-(29-P$1)") (class "Default")
      (node (ref "29") (pin "A") (pinfunction "P$1_A") (pintype "bidirectional"))
      (node (ref "RN8") (pin "2") (pinfunction "2_2") (pintype "passive"))
    )
    (net (code "47") (name "Net-(30-P$1)") (class "Default")
      (node (ref "30") (pin "A") (pinfunction "P$1_A") (pintype "bidirectional"))
      (node (ref "RN8") (pin "3") (pinfunction "3_3") (pintype "passive"))
    )
    (net (code "48") (name "Net-(31-P$1)") (class "Default")
      (node (ref "31") (pin "A") (pinfunction "P$1_A") (pintype "bidirectional"))
      (node (ref "RN8") (pin "4") (pinfunction "4_4") (pintype "passive"))
    )
    (net (code "49") (name "Net-(32-P$1)") (class "Default")
      (node (ref "32") (pin "A") (pinfunction "P$1_A") (pintype "bidirectional"))
      (node (ref "RN9") (pin "1") (pinfunction "1_1") (pintype "passive"))
    )
    (net (code "50") (name "Net-(33-P$1)") (class "Default")
      (node (ref "33") (pin "A") (pinfunction "P$1_A") (pintype "bidirectional"))
      (node (ref "RN9") (pin "2") (pinfunction "2_2") (pintype "passive"))
    )
    (net (code "51") (name "Net-(34-P$1)") (class "Default")
      (node (ref "34") (pin "A") (pinfunction "P$1_A") (pintype "bidirectional"))
      (node (ref "RN9") (pin "3") (pinfunction "3_3") (pintype "passive"))
    )
    (net (code "52") (name "Net-(35-P$1)") (class "Default")
      (node (ref "35") (pin "A") (pinfunction "P$1_A") (pintype "bidirectional"))
      (node (ref "RN9") (pin "4") (pinfunction "4_4") (pintype "passive"))
    )
    (net (code "53") (name "Net-(36-P$1)") (class "Default")
      (node (ref "36") (pin "A") (pinfunction "P$1_A") (pintype "bidirectional"))
      (node (ref "RN10") (pin "1") (pinfunction "1_1") (pintype "passive"))
    )
    (net (code "54") (name "Net-(37-P$1)") (class "Default")
      (node (ref "37") (pin "A") (pinfunction "P$1_A") (pintype "bidirectional"))
      (node (ref "RN10") (pin "2") (pinfunction "2_2") (pintype "passive"))
    )
    (net (code "55") (name "Net-(38-P$1)") (class "Default")
      (node (ref "38") (pin "A") (pinfunction "P$1_A") (pintype "bidirectional"))
      (node (ref "RN10") (pin "3") (pinfunction "3_3") (pintype "passive"))
    )
    (net (code "56") (name "Net-(39-P$1)") (class "Default")
      (node (ref "39") (pin "A") (pinfunction "P$1_A") (pintype "bidirectional"))
      (node (ref "RN10") (pin "4") (pinfunction "4_4") (pintype "passive"))
    )
    (net (code "57") (name "Net-(DIAG-PadA)") (class "Default")
      (node (ref "DIAG") (pin "A") (pinfunction "A_A") (pintype "passive"))
      (node (ref "R1") (pin "2") (pinfunction "2_2") (pintype "passive"))
    )
    (net (code "58") (name "Net-(IC1-PB3(MOSI{slash}OC2))") (class "Default")
      (node (ref "IC1") (pin "15") (pinfunction "PB3(MOSI/OC2)_15") (pintype "bidirectional"))
      (node (ref "ICSP") (pin "4") (pinfunction "MOSI_4") (pintype "bidirectional"))
    )
    (net (code "59") (name "Net-(IC1-PB4(MISO))") (class "Default")
      (node (ref "IC1") (pin "16") (pinfunction "PB4(MISO)_16") (pintype "bidirectional"))
      (node (ref "ICSP") (pin "5") (pinfunction "MISO_5") (pintype "bidirectional"))
    )
    (net (code "60") (name "Net-(IC1-PB6(XTAL1{slash}TOSC1))") (class "Default")
      (node (ref "C9") (pin "2") (pinfunction "2_2") (pintype "passive"))
      (node (ref "IC1") (pin "7") (pinfunction "PB6(XTAL1/TOSC1)_7") (pintype "bidirectional"))
      (node (ref "X1") (pin "2") (pinfunction "2_2") (pintype "passive"))
    )
    (net (code "61") (name "Net-(IC1-PB7(XTAL2{slash}TOSC2))") (class "Default")
      (node (ref "C10") (pin "2") (pinfunction "2_2") (pintype "passive"))
      (node (ref "IC1") (pin "8") (pinfunction "PB7(XTAL2/TOSC2)_8") (pintype "bidirectional"))
      (node (ref "X1") (pin "1") (pinfunction "1_1") (pintype "passive"))
    )
    (net (code "62") (name "Net-(IC1-PC6({slash}RESET))") (class "Default")
      (node (ref "IC1") (pin "29") (pinfunction "PC6(/RESET)_29") (pintype "bidirectional"))
      (node (ref "ICSP") (pin "1") (pinfunction "RESET_1") (pintype "bidirectional"))
      (node (ref "RESET") (pin "1") (pinfunction "S_1") (pintype "passive"))
      (node (ref "SERIALPROG") (pin "1") (pinfunction "1_1") (pintype "passive"))
    )
    (net (code "63") (name "Net-(IC1-PD0(RXD))") (class "Default")
      (node (ref "IC1") (pin "30") (pinfunction "PD0(RXD)_30") (pintype "bidirectional"))
      (node (ref "SERIALPROG") (pin "3") (pinfunction "3_3") (pintype "passive"))
    )
    (net (code "64") (name "Net-(IC1-PD1(TXD))") (class "Default")
      (node (ref "IC1") (pin "31") (pinfunction "PD1(TXD)_31") (pintype "bidirectional"))
      (node (ref "SERIALPROG") (pin "2") (pinfunction "2_2") (pintype "passive"))
    )
    (net (code "65") (name "Net-(IC3-QA)") (class "Default")
      (node (ref "IC3") (pin "15") (pinfunction "QA_15") (pintype "tri_state"))
      (node (ref "RN1") (pin "8") (pinfunction "8_8") (pintype "passive"))
    )
    (net (code "66") (name "Net-(IC3-QB)") (class "Default")
      (node (ref "IC3") (pin "1") (pinfunction "QB_1") (pintype "tri_state"))
      (node (ref "RN1") (pin "7") (pinfunction "7_7") (pintype "passive"))
    )
    (net (code "67") (name "Net-(IC3-QC)") (class "Default")
      (node (ref "IC3") (pin "2") (pinfunction "QC_2") (pintype "tri_state"))
      (node (ref "RN1") (pin "6") (pinfunction "6_6") (pintype "passive"))
    )
    (net (code "68") (name "Net-(IC3-QD)") (class "Default")
      (node (ref "IC3") (pin "3") (pinfunction "QD_3") (pintype "tri_state"))
      (node (ref "RN1") (pin "5") (pinfunction "5_5") (pintype "passive"))
    )
    (net (code "69") (name "Net-(IC3-QE)") (class "Default")
      (node (ref "IC3") (pin "4") (pinfunction "QE_4") (pintype "tri_state"))
      (node (ref "RN2") (pin "8") (pinfunction "8_8") (pintype "passive"))
    )
    (net (code "70") (name "Net-(IC3-QF)") (class "Default")
      (node (ref "IC3") (pin "5") (pinfunction "QF_5") (pintype "tri_state"))
      (node (ref "RN2") (pin "7") (pinfunction "7_7") (pintype "passive"))
    )
    (net (code "71") (name "Net-(IC3-QG)") (class "Default")
      (node (ref "IC3") (pin "6") (pinfunction "QG_6") (pintype "tri_state"))
      (node (ref "RN2") (pin "6") (pinfunction "6_6") (pintype "passive"))
    )
    (net (code "72") (name "Net-(IC3-QH)") (class "Default")
      (node (ref "IC3") (pin "7") (pinfunction "QH_7") (pintype "tri_state"))
      (node (ref "RN2") (pin "5") (pinfunction "5_5") (pintype "passive"))
    )
    (net (code "73") (name "Net-(IC4-QA)") (class "Default")
      (node (ref "IC4") (pin "15") (pinfunction "QA_15") (pintype "tri_state"))
      (node (ref "RN3") (pin "8") (pinfunction "8_8") (pintype "passive"))
    )
    (net (code "74") (name "Net-(IC4-QB)") (class "Default")
      (node (ref "IC4") (pin "1") (pinfunction "QB_1") (pintype "tri_state"))
      (node (ref "RN3") (pin "7") (pinfunction "7_7") (pintype "passive"))
    )
    (net (code "75") (name "Net-(IC4-QC)") (class "Default")
      (node (ref "IC4") (pin "2") (pinfunction "QC_2") (pintype "tri_state"))
      (node (ref "RN3") (pin "6") (pinfunction "6_6") (pintype "passive"))
    )
    (net (code "76") (name "Net-(IC4-QD)") (class "Default")
      (node (ref "IC4") (pin "3") (pinfunction "QD_3") (pintype "tri_state"))
      (node (ref "RN3") (pin "5") (pinfunction "5_5") (pintype "passive"))
    )
    (net (code "77") (name "Net-(IC4-QE)") (class "Default")
      (node (ref "IC4") (pin "4") (pinfunction "QE_4") (pintype "tri_state"))
      (node (ref "RN4") (pin "8") (pinfunction "8_8") (pintype "passive"))
    )
    (net (code "78") (name "Net-(IC4-QF)") (class "Default")
      (node (ref "IC4") (pin "5") (pinfunction "QF_5") (pintype "tri_state"))
      (node (ref "RN4") (pin "7") (pinfunction "7_7") (pintype "passive"))
    )
    (net (code "79") (name "Net-(IC4-QG)") (class "Default")
      (node (ref "IC4") (pin "6") (pinfunction "QG_6") (pintype "tri_state"))
      (node (ref "RN4") (pin "6") (pinfunction "6_6") (pintype "passive"))
    )
    (net (code "80") (name "Net-(IC4-QH)") (class "Default")
      (node (ref "IC4") (pin "7") (pinfunction "QH_7") (pintype "tri_state"))
      (node (ref "RN4") (pin "5") (pinfunction "5_5") (pintype "passive"))
    )
    (net (code "81") (name "Net-(IC5-QA)") (class "Default")
      (node (ref "IC5") (pin "15") (pinfunction "QA_15") (pintype "tri_state"))
      (node (ref "RN5") (pin "8") (pinfunction "8_8") (pintype "passive"))
    )
    (net (code "82") (name "Net-(IC5-QB)") (class "Default")
      (node (ref "IC5") (pin "1") (pinfunction "QB_1") (pintype "tri_state"))
      (node (ref "RN5") (pin "7") (pinfunction "7_7") (pintype "passive"))
    )
    (net (code "83") (name "Net-(IC5-QC)") (class "Default")
      (node (ref "IC5") (pin "2") (pinfunction "QC_2") (pintype "tri_state"))
      (node (ref "RN5") (pin "6") (pinfunction "6_6") (pintype "passive"))
    )
    (net (code "84") (name "Net-(IC5-QD)") (class "Default")
      (node (ref "IC5") (pin "3") (pinfunction "QD_3") (pintype "tri_state"))
      (node (ref "RN5") (pin "5") (pinfunction "5_5") (pintype "passive"))
    )
    (net (code "85") (name "Net-(IC5-QE)") (class "Default")
      (node (ref "IC5") (pin "4") (pinfunction "QE_4") (pintype "tri_state"))
      (node (ref "RN6") (pin "8") (pinfunction "8_8") (pintype "passive"))
    )
    (net (code "86") (name "Net-(IC5-QF)") (class "Default")
      (node (ref "IC5") (pin "5") (pinfunction "QF_5") (pintype "tri_state"))
      (node (ref "RN6") (pin "7") (pinfunction "7_7") (pintype "passive"))
    )
    (net (code "87") (name "Net-(IC5-QG)") (class "Default")
      (node (ref "IC5") (pin "6") (pinfunction "QG_6") (pintype "tri_state"))
      (node (ref "RN6") (pin "6") (pinfunction "6_6") (pintype "passive"))
    )
    (net (code "88") (name "Net-(IC5-QH)") (class "Default")
      (node (ref "IC5") (pin "7") (pinfunction "QH_7") (pintype "tri_state"))
      (node (ref "RN6") (pin "5") (pinfunction "5_5") (pintype "passive"))
    )
    (net (code "89") (name "Net-(IC6-QA)") (class "Default")
      (node (ref "IC6") (pin "15") (pinfunction "QA_15") (pintype "tri_state"))
      (node (ref "RN7") (pin "8") (pinfunction "8_8") (pintype "passive"))
    )
    (net (code "90") (name "Net-(IC6-QB)") (class "Default")
      (node (ref "IC6") (pin "1") (pinfunction "QB_1") (pintype "tri_state"))
      (node (ref "RN7") (pin "7") (pinfunction "7_7") (pintype "passive"))
    )
    (net (code "91") (name "Net-(IC6-QC)") (class "Default")
      (node (ref "IC6") (pin "2") (pinfunction "QC_2") (pintype "tri_state"))
      (node (ref "RN7") (pin "6") (pinfunction "6_6") (pintype "passive"))
    )
    (net (code "92") (name "Net-(IC6-QD)") (class "Default")
      (node (ref "IC6") (pin "3") (pinfunction "QD_3") (pintype "tri_state"))
      (node (ref "RN7") (pin "5") (pinfunction "5_5") (pintype "passive"))
    )
    (net (code "93") (name "Net-(IC6-QE)") (class "Default")
      (node (ref "IC6") (pin "4") (pinfunction "QE_4") (pintype "tri_state"))
      (node (ref "RN8") (pin "8") (pinfunction "8_8") (pintype "passive"))
    )
    (net (code "94") (name "Net-(IC6-QF)") (class "Default")
      (node (ref "IC6") (pin "5") (pinfunction "QF_5") (pintype "tri_state"))
      (node (ref "RN8") (pin "7") (pinfunction "7_7") (pintype "passive"))
    )
    (net (code "95") (name "Net-(IC6-QG)") (class "Default")
      (node (ref "IC6") (pin "6") (pinfunction "QG_6") (pintype "tri_state"))
      (node (ref "RN8") (pin "6") (pinfunction "6_6") (pintype "passive"))
    )
    (net (code "96") (name "Net-(IC6-QH)") (class "Default")
      (node (ref "IC6") (pin "7") (pinfunction "QH_7") (pintype "tri_state"))
      (node (ref "RN8") (pin "5") (pinfunction "5_5") (pintype "passive"))
    )
    (net (code "97") (name "Net-(IC7-QA)") (class "Default")
      (node (ref "IC7") (pin "15") (pinfunction "QA_15") (pintype "tri_state"))
      (node (ref "RN9") (pin "8") (pinfunction "8_8") (pintype "passive"))
    )
    (net (code "98") (name "Net-(IC7-QB)") (class "Default")
      (node (ref "IC7") (pin "1") (pinfunction "QB_1") (pintype "tri_state"))
      (node (ref "RN9") (pin "7") (pinfunction "7_7") (pintype "passive"))
    )
    (net (code "99") (name "Net-(IC7-QC)") (class "Default")
      (node (ref "IC7") (pin "2") (pinfunction "QC_2") (pintype "tri_state"))
      (node (ref "RN9") (pin "6") (pinfunction "6_6") (pintype "passive"))
    )
    (net (code "100") (name "Net-(IC7-QD)") (class "Default")
      (node (ref "IC7") (pin "3") (pinfunction "QD_3") (pintype "tri_state"))
      (node (ref "RN9") (pin "5") (pinfunction "5_5") (pintype "passive"))
    )
    (net (code "101") (name "Net-(IC7-QE)") (class "Default")
      (node (ref "IC7") (pin "4") (pinfunction "QE_4") (pintype "tri_state"))
      (node (ref "RN10") (pin "8") (pinfunction "8_8") (pintype "passive"))
    )
    (net (code "102") (name "Net-(IC7-QF)") (class "Default")
      (node (ref "IC7") (pin "5") (pinfunction "QF_5") (pintype "tri_state"))
      (node (ref "RN10") (pin "7") (pinfunction "7_7") (pintype "passive"))
    )
    (net (code "103") (name "Net-(IC7-QG)") (class "Default")
      (node (ref "IC7") (pin "6") (pinfunction "QG_6") (pintype "tri_state"))
      (node (ref "RN10") (pin "6") (pinfunction "6_6") (pintype "passive"))
    )
    (net (code "104") (name "Net-(IC7-QH)") (class "Default")
      (node (ref "IC7") (pin "7") (pinfunction "QH_7") (pintype "tri_state"))
      (node (ref "RN10") (pin "5") (pinfunction "5_5") (pintype "passive"))
    )
    (net (code "105") (name "unconnected-(A-P1-Pad4)") (class "Default")
      (node (ref "A") (pin "4") (pinfunction "P1_4") (pintype "passive"))
    )
    (net (code "106") (name "unconnected-(A-S1-Pad2)") (class "Default")
      (node (ref "A") (pin "2") (pinfunction "S1_2") (pintype "passive"))
    )
    (net (code "107") (name "unconnected-(B-P1-Pad4)") (class "Default")
      (node (ref "B") (pin "4") (pinfunction "P1_4") (pintype "passive"))
    )
    (net (code "108") (name "unconnected-(B-S1-Pad2)") (class "Default")
      (node (ref "B") (pin "2") (pinfunction "S1_2") (pintype "passive"))
    )
    (net (code "109") (name "unconnected-(C-P1-Pad4)") (class "Default")
      (node (ref "C") (pin "4") (pinfunction "P1_4") (pintype "passive"))
    )
    (net (code "110") (name "unconnected-(C-S1-Pad2)") (class "Default")
      (node (ref "C") (pin "2") (pinfunction "S1_2") (pintype "passive"))
    )
    (net (code "111") (name "unconnected-(IC1-ADC6-Pad19)") (class "Default")
      (node (ref "IC1") (pin "19") (pinfunction "ADC6_19") (pintype "bidirectional"))
    )
    (net (code "112") (name "unconnected-(IC1-ADC7-Pad22)") (class "Default")
      (node (ref "IC1") (pin "22") (pinfunction "ADC7_22") (pintype "bidirectional"))
    )
    (net (code "113") (name "unconnected-(IC1-PC5(ADC5{slash}SCL)-Pad28)") (class "Default")
      (node (ref "IC1") (pin "28") (pinfunction "PC5(ADC5/SCL)_28") (pintype "bidirectional"))
    )
    (net (code "114") (name "unconnected-(IC1-PD3(INT1)-Pad1)") (class "Default")
      (node (ref "IC1") (pin "1") (pinfunction "PD3(INT1)_1") (pintype "bidirectional"))
    )
    (net (code "115") (name "unconnected-(IC1-PD7(AIN1)-Pad11)") (class "Default")
      (node (ref "IC1") (pin "11") (pinfunction "PD7(AIN1)_11") (pintype "bidirectional"))
    )
    (net (code "116") (name "unconnected-(IC3-QH*-Pad9)") (class "Default")
      (node (ref "IC3") (pin "9") (pinfunction "QH*_9") (pintype "tri_state"))
    )
    (net (code "117") (name "unconnected-(IC4-QH*-Pad9)") (class "Default")
      (node (ref "IC4") (pin "9") (pinfunction "QH*_9") (pintype "tri_state"))
    )
    (net (code "118") (name "unconnected-(IC5-QH*-Pad9)") (class "Default")
      (node (ref "IC5") (pin "9") (pinfunction "QH*_9") (pintype "tri_state"))
    )
    (net (code "119") (name "unconnected-(IC6-QH*-Pad9)") (class "Default")
      (node (ref "IC6") (pin "9") (pinfunction "QH*_9") (pintype "tri_state"))
    )
    (net (code "120") (name "unconnected-(IC7-QH*-Pad9)") (class "Default")
      (node (ref "IC7") (pin "9") (pinfunction "QH*_9") (pintype "tri_state"))
    )
    (net (code "121") (name "unconnected-(RESET-P1-Pad4)") (class "Default")
      (node (ref "RESET") (pin "4") (pinfunction "P1_4") (pintype "passive"))
    )
    (net (code "122") (name "unconnected-(RESET-S1-Pad2)") (class "Default")
      (node (ref "RESET") (pin "2") (pinfunction "S1_2") (pintype "passive"))
    )
  )
)
